# Fan-Module.net
KiCad netlist of a schematic drawn in EAGLE
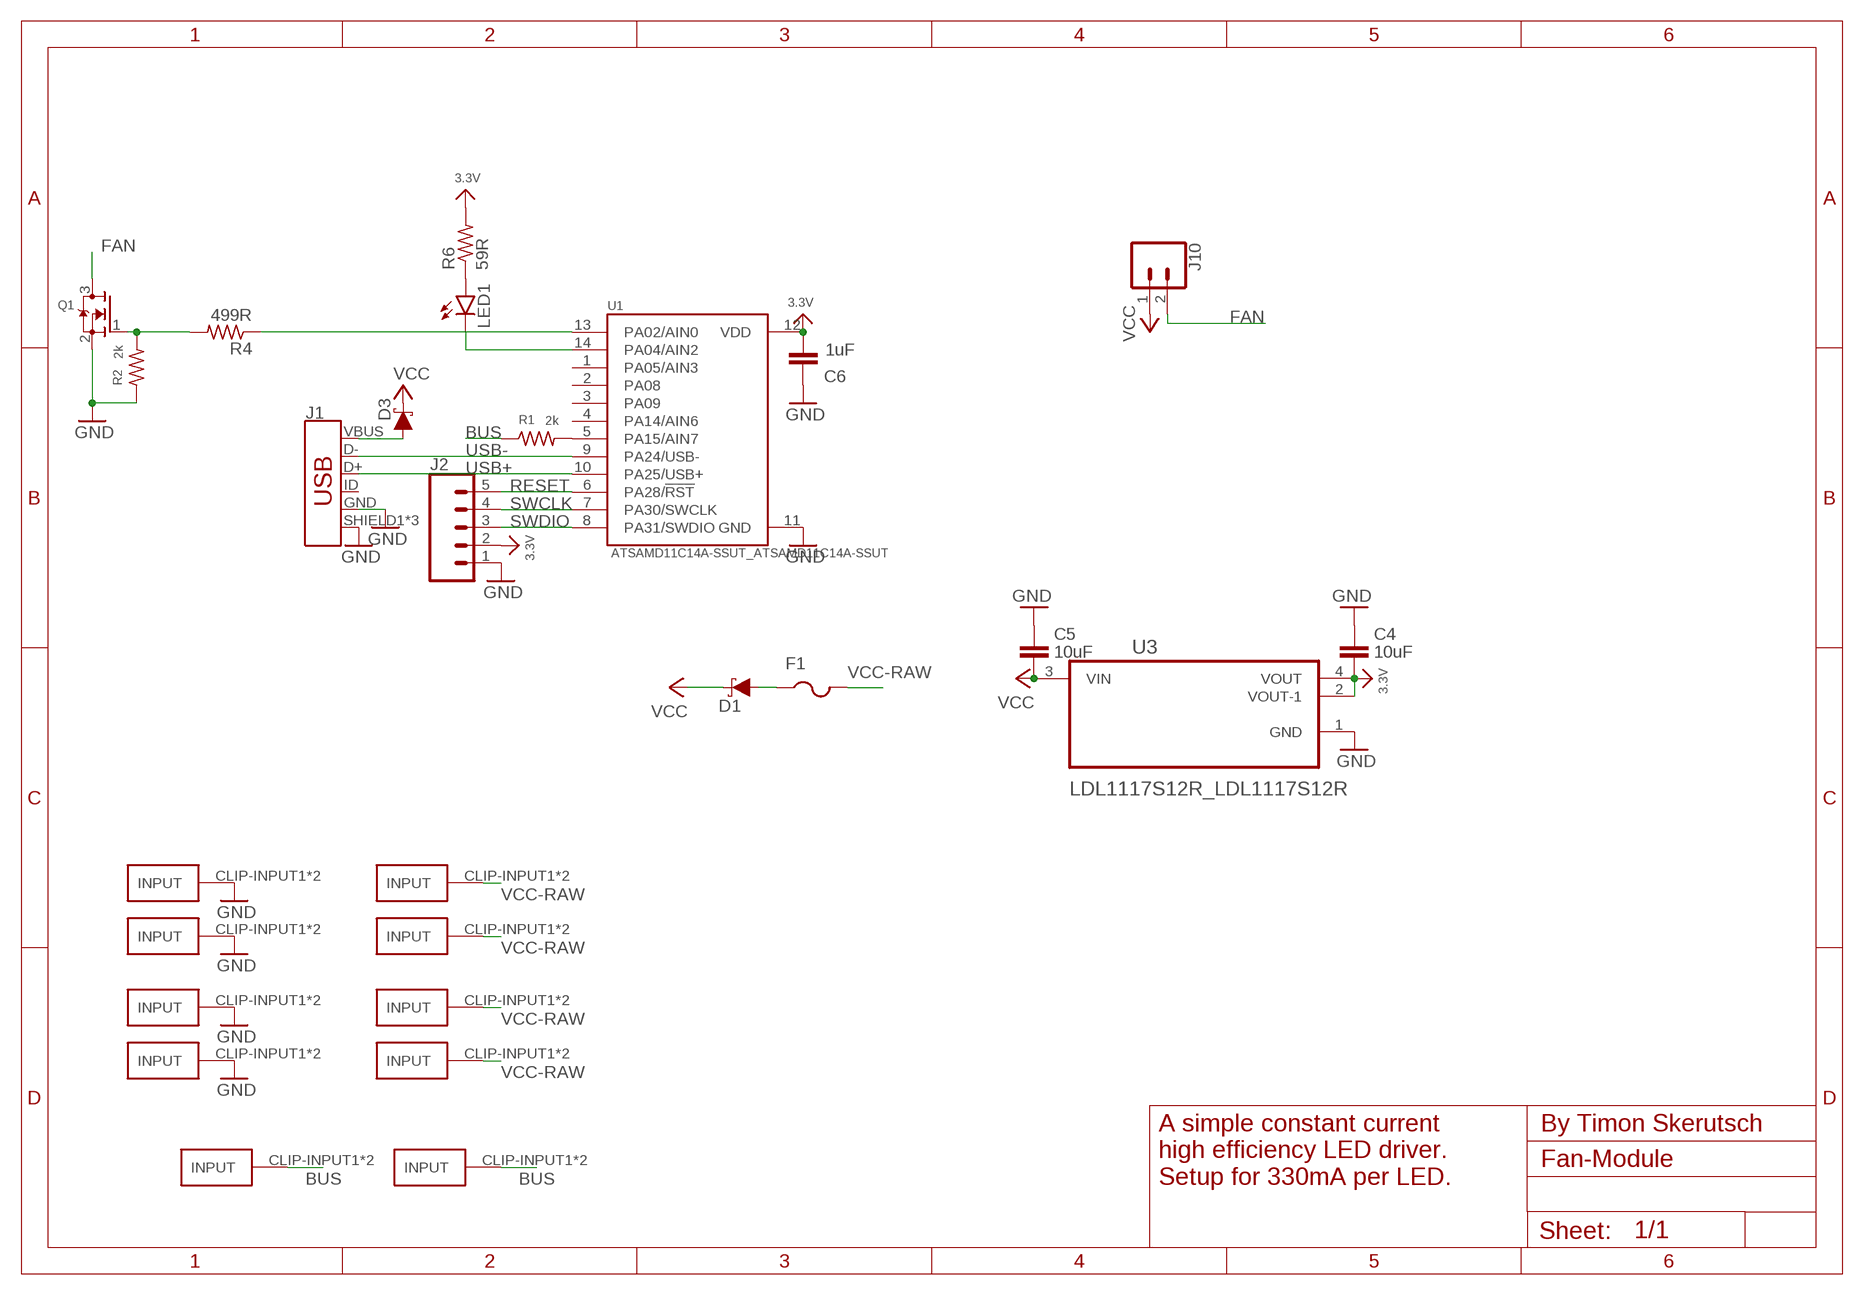
[diagram p0: schematic, sheet 1]

(export (version "E")
  (design (tool "Eeschema 10.0.6"))
  (components
    (comp (ref "C4")
      (value "10uF")
      (footprint "eagle-import:C0603")
      (libsource (lib "eagle-import") (part "C-EUC0603"))
    )
    (comp (ref "C5")
      (value "10uF")
      (footprint "eagle-import:C0603")
      (libsource (lib "eagle-import") (part "C-EUC0603"))
    )
    (comp (ref "C6")
      (value "1uF")
      (footprint "eagle-import:C0603")
      (libsource (lib "eagle-import") (part "C-EUC0603"))
    )
    (comp (ref "D1")
      (value "3A/40V/500mV")
      (footprint "eagle-import:SMA-DIODE")
      (libsource (lib "eagle-import") (part "DIODE-SCHOTTKY-B340A"))
    )
    (comp (ref "D3")
      (value "3A/40V/500mV")
      (footprint "eagle-import:SMA-DIODE")
      (libsource (lib "eagle-import") (part "DIODE-SCHOTTKY-B340A"))
    )
    (comp (ref "F1")
      (value "PTCFUSE-1812")
      (footprint "eagle-import:1812")
      (libsource (lib "eagle-import") (part "PTCFUSE-1812"))
    )
    (comp (ref "GND-CLIP")
      (value "FUSE-HOLDER-5X20MM")
      (footprint "eagle-import:FUSE-HOLDER-5X20MM")
      (libsource (lib "eagle-import") (part "FUSE-HOLDER-5X20MM"))
    )
    (comp (ref "GND-CLIP1")
      (value "FUSE-HOLDER-5X20MM")
      (footprint "eagle-import:FUSE-HOLDER-5X20MM")
      (libsource (lib "eagle-import") (part "FUSE-HOLDER-5X20MM"))
    )
    (comp (ref "GND-CLIP2")
      (value "FUSE-HOLDER-5X20MM")
      (footprint "eagle-import:FUSE-HOLDER-5X20MM")
      (libsource (lib "eagle-import") (part "FUSE-HOLDER-5X20MM"))
    )
    (comp (ref "GND-CLIP3")
      (value "FUSE-HOLDER-5X20MM")
      (footprint "eagle-import:FUSE-HOLDER-5X20MM")
      (libsource (lib "eagle-import") (part "FUSE-HOLDER-5X20MM"))
    )
    (comp (ref "J1")
      (value "USB_MICRO-B_FEMALE-SMT")
      (footprint "eagle-import:USB-B-MICRO-SMD")
      (libsource (lib "eagle-import") (part "USB_MICRO-B_FEMALE-SMT"))
    )
    (comp (ref "J2")
      (value "CONN_05")
      (footprint "eagle-import:1X05")
      (libsource (lib "eagle-import") (part "CONN_05"))
    )
    (comp (ref "J10")
      (value "CONN_02PTH3")
      (footprint "eagle-import:1X02_LONGPADS")
      (libsource (lib "eagle-import") (part "CONN_02PTH3"))
    )
    (comp (ref "LED1")
      (value "LEDCHIPLED_0805")
      (footprint "eagle-import:CHIPLED_0805")
      (libsource (lib "eagle-import") (part "LEDCHIPLED_0805"))
    )
    (comp (ref "PWM-CLIP")
      (value "FUSE-HOLDER-5X20MM")
      (footprint "eagle-import:FUSE-HOLDER-5X20MM")
      (libsource (lib "eagle-import") (part "FUSE-HOLDER-5X20MM"))
    )
    (comp (ref "PWM-CLIP1")
      (value "FUSE-HOLDER-5X20MM")
      (footprint "eagle-import:FUSE-HOLDER-5X20MM")
      (libsource (lib "eagle-import") (part "FUSE-HOLDER-5X20MM"))
    )
    (comp (ref "Q1")
      (value "MOSFET-NWIDE")
      (footprint "eagle-import:SOT23-WIDE")
      (libsource (lib "eagle-import") (part "MOSFET-NWIDE"))
    )
    (comp (ref "R1")
      (value "2k")
      (footprint "eagle-import:R1206")
      (libsource (lib "eagle-import") (part "R-US_R1206"))
    )
    (comp (ref "R2")
      (value "2k")
      (footprint "eagle-import:R1206")
      (libsource (lib "eagle-import") (part "R-US_R1206"))
    )
    (comp (ref "R4")
      (value "499R")
      (footprint "eagle-import:R0805")
      (libsource (lib "eagle-import") (part "R-US_R0805"))
    )
    (comp (ref "R6")
      (value "59R")
      (footprint "eagle-import:R0805")
      (libsource (lib "eagle-import") (part "R-US_R0805"))
    )
    (comp (ref "U1")
      (value "ATSAMD11C14A-SSUT_ATSAMD11C14A-SSUT")
      (footprint "eagle-import:ATSAMD11C14A-SSUT_SOIC127P600X160-14N")
      (fields (field (name "MF") "Microchip") (field (name "MP") "ATSAMD11C14A-SSUT"))
      (libsource (lib "eagle-import") (part "ATSAMD11C14A-SSUT_ATSAMD11C14A-SSUT"))
    )
    (comp (ref "U3")
      (value "LDL1117S12R_LDL1117S12R")
      (footprint "eagle-import:LDL1117S12R_SOT230P700X180-4N")
      (fields (field (name "MF") "STMicroelectronics") (field (name "MP") "LDL1117S12R"))
      (libsource (lib "eagle-import") (part "LDL1117S12R_LDL1117S12R"))
    )
    (comp (ref "VCC-CLIP")
      (value "FUSE-HOLDER-5X20MM")
      (footprint "eagle-import:FUSE-HOLDER-5X20MM")
      (libsource (lib "eagle-import") (part "FUSE-HOLDER-5X20MM"))
    )
    (comp (ref "VCC-CLIP1")
      (value "FUSE-HOLDER-5X20MM")
      (footprint "eagle-import:FUSE-HOLDER-5X20MM")
      (libsource (lib "eagle-import") (part "FUSE-HOLDER-5X20MM"))
    )
    (comp (ref "VCC-CLIP2")
      (value "FUSE-HOLDER-5X20MM")
      (footprint "eagle-import:FUSE-HOLDER-5X20MM")
      (libsource (lib "eagle-import") (part "FUSE-HOLDER-5X20MM"))
    )
    (comp (ref "VCC-CLIP3")
      (value "FUSE-HOLDER-5X20MM")
      (footprint "eagle-import:FUSE-HOLDER-5X20MM")
      (libsource (lib "eagle-import") (part "FUSE-HOLDER-5X20MM"))
    )
  )
  (nets
    (net (code "1") (name "/BUS") (class "Default")
      (node (ref "PWM-CLIP") (pin "CLIP-INPUT1") (pinfunction "INPUT_CLIP-INPUT1") (pintype "bidirectional"))
      (node (ref "PWM-CLIP") (pin "CLIP-INPUT2") (pinfunction "INPUT_CLIP-INPUT2") (pintype "bidirectional"))
      (node (ref "PWM-CLIP1") (pin "CLIP-INPUT1") (pinfunction "INPUT_CLIP-INPUT1") (pintype "bidirectional"))
      (node (ref "PWM-CLIP1") (pin "CLIP-INPUT2") (pinfunction "INPUT_CLIP-INPUT2") (pintype "bidirectional"))
      (node (ref "R1") (pin "1") (pinfunction "1_1") (pintype "passive"))
    )
    (net (code "2") (name "/FAN") (class "Default")
      (node (ref "J10") (pin "2") (pinfunction "2_2") (pintype "passive"))
      (node (ref "Q1") (pin "3") (pinfunction "D_3") (pintype "bidirectional"))
    )
    (net (code "3") (name "/RESET") (class "Default")
      (node (ref "J2") (pin "5") (pinfunction "5_5") (pintype "passive"))
      (node (ref "U1") (pin "6") (pinfunction "PA28/~{RST}_6") (pintype "bidirectional"))
    )
    (net (code "4") (name "/SWCLK") (class "Default")
      (node (ref "J2") (pin "4") (pinfunction "4_4") (pintype "passive"))
      (node (ref "U1") (pin "7") (pinfunction "PA30/SWCLK_7") (pintype "bidirectional"))
    )
    (net (code "5") (name "/SWDIO") (class "Default")
      (node (ref "J2") (pin "3") (pinfunction "3_3") (pintype "passive"))
      (node (ref "U1") (pin "8") (pinfunction "PA31/SWDIO_8") (pintype "bidirectional"))
    )
    (net (code "6") (name "/USB+") (class "Default")
      (node (ref "J1") (pin "D+") (pinfunction "D+_D+") (pintype "bidirectional"))
      (node (ref "U1") (pin "10") (pinfunction "PA25/USB+_10") (pintype "bidirectional"))
    )
    (net (code "7") (name "/USB-") (class "Default")
      (node (ref "J1") (pin "D-") (pinfunction "D-_D-") (pintype "bidirectional"))
      (node (ref "U1") (pin "9") (pinfunction "PA24/USB-_9") (pintype "bidirectional"))
    )
    (net (code "8") (name "/VCC-RAW") (class "Default")
      (node (ref "F1") (pin "2") (pinfunction "2_2") (pintype "passive"))
      (node (ref "VCC-CLIP") (pin "CLIP-INPUT1") (pinfunction "INPUT_CLIP-INPUT1") (pintype "bidirectional"))
      (node (ref "VCC-CLIP") (pin "CLIP-INPUT2") (pinfunction "INPUT_CLIP-INPUT2") (pintype "bidirectional"))
      (node (ref "VCC-CLIP1") (pin "CLIP-INPUT1") (pinfunction "INPUT_CLIP-INPUT1") (pintype "bidirectional"))
      (node (ref "VCC-CLIP1") (pin "CLIP-INPUT2") (pinfunction "INPUT_CLIP-INPUT2") (pintype "bidirectional"))
      (node (ref "VCC-CLIP2") (pin "CLIP-INPUT1") (pinfunction "INPUT_CLIP-INPUT1") (pintype "bidirectional"))
      (node (ref "VCC-CLIP2") (pin "CLIP-INPUT2") (pinfunction "INPUT_CLIP-INPUT2") (pintype "bidirectional"))
      (node (ref "VCC-CLIP3") (pin "CLIP-INPUT1") (pinfunction "INPUT_CLIP-INPUT1") (pintype "bidirectional"))
      (node (ref "VCC-CLIP3") (pin "CLIP-INPUT2") (pinfunction "INPUT_CLIP-INPUT2") (pintype "bidirectional"))
    )
    (net (code "9") (name "3.3V") (class "Default")
      (node (ref "C4") (pin "2") (pinfunction "2_2") (pintype "passive"))
      (node (ref "C6") (pin "2") (pinfunction "2_2") (pintype "passive"))
      (node (ref "J2") (pin "2") (pinfunction "2_2") (pintype "passive"))
      (node (ref "R6") (pin "2") (pinfunction "2_2") (pintype "passive"))
      (node (ref "U1") (pin "12") (pinfunction "VDD_12") (pintype "power_in"))
      (node (ref "U3") (pin "2") (pinfunction "VOUT-1_2") (pintype "output"))
      (node (ref "U3") (pin "4") (pinfunction "VOUT_4") (pintype "output"))
    )
    (net (code "10") (name "GND") (class "Default")
      (node (ref "C4") (pin "1") (pinfunction "1_1") (pintype "passive"))
      (node (ref "C5") (pin "1") (pinfunction "1_1") (pintype "passive"))
      (node (ref "C6") (pin "1") (pinfunction "1_1") (pintype "passive"))
      (node (ref "GND-CLIP") (pin "CLIP-INPUT1") (pinfunction "INPUT_CLIP-INPUT1") (pintype "bidirectional"))
      (node (ref "GND-CLIP") (pin "CLIP-INPUT2") (pinfunction "INPUT_CLIP-INPUT2") (pintype "bidirectional"))
      (node (ref "GND-CLIP1") (pin "CLIP-INPUT1") (pinfunction "INPUT_CLIP-INPUT1") (pintype "bidirectional"))
      (node (ref "GND-CLIP1") (pin "CLIP-INPUT2") (pinfunction "INPUT_CLIP-INPUT2") (pintype "bidirectional"))
      (node (ref "GND-CLIP2") (pin "CLIP-INPUT1") (pinfunction "INPUT_CLIP-INPUT1") (pintype "bidirectional"))
      (node (ref "GND-CLIP2") (pin "CLIP-INPUT2") (pinfunction "INPUT_CLIP-INPUT2") (pintype "bidirectional"))
      (node (ref "GND-CLIP3") (pin "CLIP-INPUT1") (pinfunction "INPUT_CLIP-INPUT1") (pintype "bidirectional"))
      (node (ref "GND-CLIP3") (pin "CLIP-INPUT2") (pinfunction "INPUT_CLIP-INPUT2") (pintype "bidirectional"))
      (node (ref "J1") (pin "GND") (pinfunction "GND_GND") (pintype "power_in"))
      (node (ref "J1") (pin "SHIELD1") (pinfunction "SHIELD_SHIELD1") (pintype "bidirectional"))
      (node (ref "J1") (pin "SHIELD2") (pinfunction "SHIELD_SHIELD2") (pintype "bidirectional"))
      (node (ref "J1") (pin "SHIELD3") (pinfunction "SHIELD_SHIELD3") (pintype "bidirectional"))
      (node (ref "J2") (pin "1") (pinfunction "1_1") (pintype "passive"))
      (node (ref "Q1") (pin "2") (pinfunction "S_2") (pintype "bidirectional"))
      (node (ref "R2") (pin "1") (pinfunction "1_1") (pintype "passive"))
      (node (ref "U1") (pin "11") (pinfunction "GND_11") (pintype "power_in"))
      (node (ref "U3") (pin "1") (pinfunction "GND_1") (pintype "power_in"))
    )
    (net (code "11") (name "Net-(D1-PadA)") (class "Default")
      (node (ref "D1") (pin "A") (pinfunction "A_A") (pintype "passive"))
      (node (ref "F1") (pin "1") (pinfunction "1_1") (pintype "passive"))
    )
    (net (code "12") (name "Net-(D3-PadA)") (class "Default")
      (node (ref "D3") (pin "A") (pinfunction "A_A") (pintype "passive"))
      (node (ref "J1") (pin "VBUS") (pinfunction "VBUS_VBUS") (pintype "power_in"))
    )
    (net (code "13") (name "Net-(LED1-PadA)") (class "Default")
      (node (ref "LED1") (pin "A") (pinfunction "A_A") (pintype "passive"))
      (node (ref "R6") (pin "1") (pinfunction "1_1") (pintype "passive"))
    )
    (net (code "14") (name "Net-(Q1-G)") (class "Default")
      (node (ref "Q1") (pin "1") (pinfunction "G_1") (pintype "bidirectional"))
      (node (ref "R2") (pin "2") (pinfunction "2_2") (pintype "passive"))
      (node (ref "R4") (pin "2") (pinfunction "2_2") (pintype "passive"))
    )
    (net (code "15") (name "Net-(U1-PA02{slash}AIN0)") (class "Default")
      (node (ref "R4") (pin "1") (pinfunction "1_1") (pintype "passive"))
      (node (ref "U1") (pin "13") (pinfunction "PA02/AIN0_13") (pintype "bidirectional"))
    )
    (net (code "16") (name "Net-(U1-PA04{slash}AIN2)") (class "Default")
      (node (ref "LED1") (pin "C") (pinfunction "C_C") (pintype "passive"))
      (node (ref "U1") (pin "14") (pinfunction "PA04/AIN2_14") (pintype "bidirectional"))
    )
    (net (code "17") (name "Net-(U1-PA15{slash}AIN7)") (class "Default")
      (node (ref "R1") (pin "2") (pinfunction "2_2") (pintype "passive"))
      (node (ref "U1") (pin "5") (pinfunction "PA15/AIN7_5") (pintype "bidirectional"))
    )
    (net (code "18") (name "VCC") (class "Default")
      (node (ref "C5") (pin "2") (pinfunction "2_2") (pintype "passive"))
      (node (ref "D1") (pin "C") (pinfunction "C_C") (pintype "passive"))
      (node (ref "D3") (pin "C") (pinfunction "C_C") (pintype "passive"))
      (node (ref "J10") (pin "1") (pinfunction "1_1") (pintype "passive"))
      (node (ref "U3") (pin "3") (pinfunction "VIN_3") (pintype "input"))
    )
    (net (code "19") (name "unconnected-(J1-PadID)") (class "Default")
      (node (ref "J1") (pin "ID") (pinfunction "ID_ID") (pintype "bidirectional"))
    )
    (net (code "20") (name "unconnected-(U1-PA05{slash}AIN3-Pad1)") (class "Default")
      (node (ref "U1") (pin "1") (pinfunction "PA05/AIN3_1") (pintype "bidirectional"))
    )
    (net (code "21") (name "unconnected-(U1-PA08-Pad2)") (class "Default")
      (node (ref "U1") (pin "2") (pinfunction "PA08_2") (pintype "bidirectional"))
    )
    (net (code "22") (name "unconnected-(U1-PA09-Pad3)") (class "Default")
      (node (ref "U1") (pin "3") (pinfunction "PA09_3") (pintype "bidirectional"))
    )
    (net (code "23") (name "unconnected-(U1-PA14{slash}AIN6-Pad4)") (class "Default")
      (node (ref "U1") (pin "4") (pinfunction "PA14/AIN6_4") (pintype "bidirectional"))
    )
  )
)
